# Controller.net
KiCad netlist of a schematic drawn in EAGLE
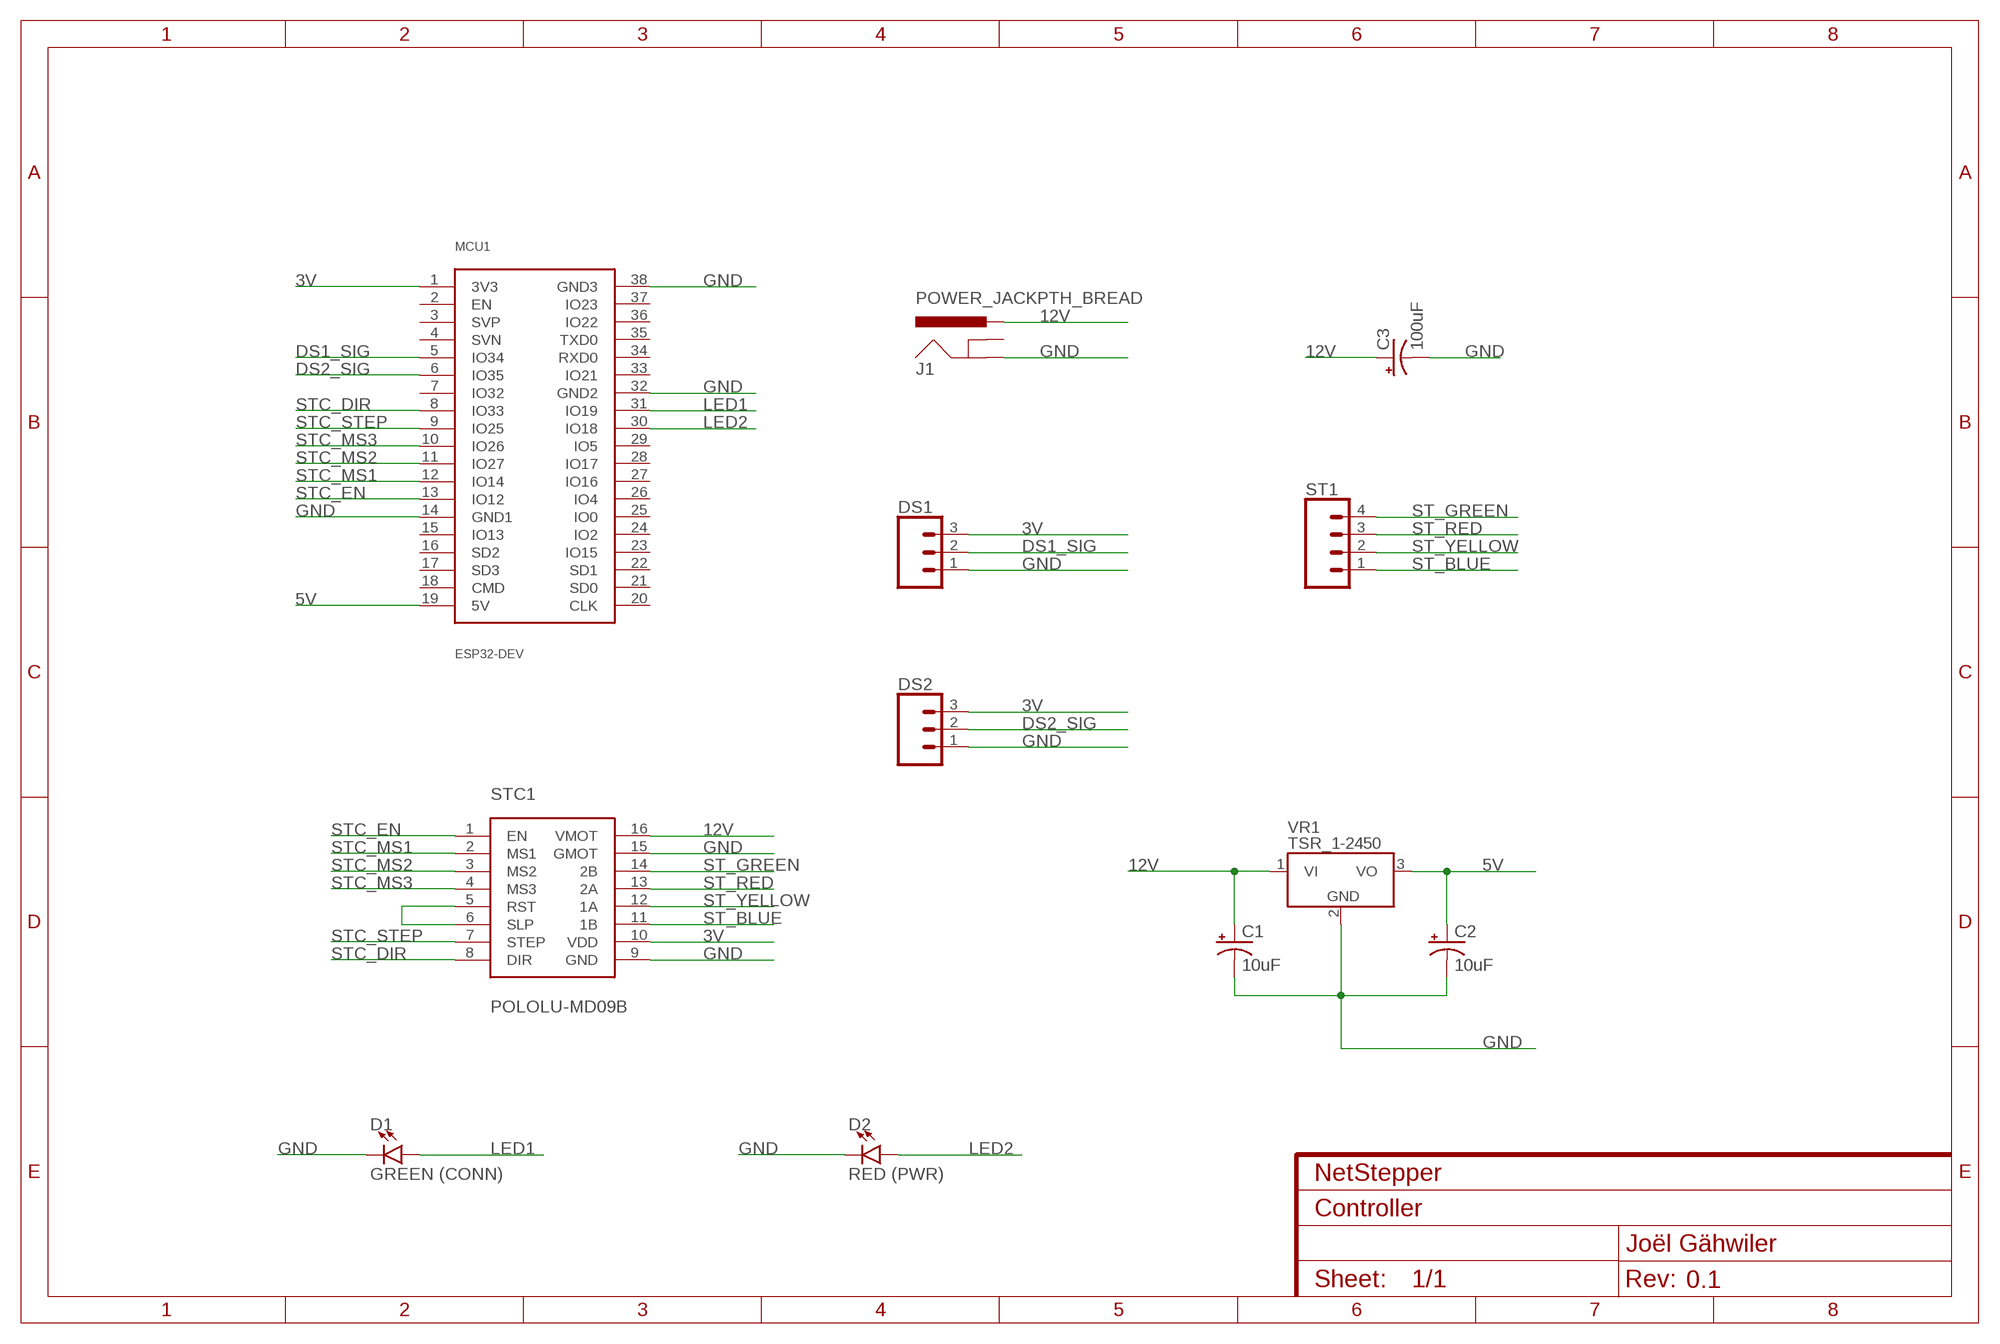
[diagram p0: schematic, sheet 1]

(export (version "E")
  (design (tool "Eeschema 10.0.6"))
  (components
    (comp (ref "C1")
      (value "10uF")
      (footprint "eagle-import:E2-5")
      (libsource (lib "eagle-import") (part "CPOL-USE2-5"))
    )
    (comp (ref "C2")
      (value "10uF")
      (footprint "eagle-import:E2-5")
      (libsource (lib "eagle-import") (part "CPOL-USE2-5"))
    )
    (comp (ref "C3")
      (value "100uF")
      (footprint "eagle-import:E2-5")
      (libsource (lib "eagle-import") (part "CPOL-USE2-5"))
    )
    (comp (ref "D1")
      (value "GREEN (CONN)")
      (footprint "eagle-import:LED_5MM")
      (libsource (lib "eagle-import") (part "LED5MM"))
    )
    (comp (ref "D2")
      (value "RED (PWR)")
      (footprint "eagle-import:LED_5MM")
      (libsource (lib "eagle-import") (part "LED5MM"))
    )
    (comp (ref "DS1")
      (value "CONN_03LONGPADS")
      (footprint "eagle-import:1X03_LONGPADS")
      (libsource (lib "eagle-import") (part "CONN_03LONGPADS"))
    )
    (comp (ref "DS2")
      (value "CONN_03LONGPADS")
      (footprint "eagle-import:1X03_LONGPADS")
      (libsource (lib "eagle-import") (part "CONN_03LONGPADS"))
    )
    (comp (ref "J1")
      (value "POWER_JACKPTH_BREAD")
      (footprint "eagle-import:POWER_JACK_PTH_BREAD")
      (libsource (lib "eagle-import") (part "POWER_JACKPTH_BREAD"))
    )
    (comp (ref "MCU1")
      (value "ESP32-DEV")
      (footprint "eagle-import:ESP32-DEV")
      (libsource (lib "eagle-import") (part "ESP32-DEV"))
    )
    (comp (ref "ST1")
      (value "CONN_04LONGPADS")
      (footprint "eagle-import:1X04_LONGPADS")
      (libsource (lib "eagle-import") (part "CONN_04LONGPADS"))
    )
    (comp (ref "STC1")
      (value "POLOLU-MD09B")
      (footprint "eagle-import:POLOLU-MD09B")
      (libsource (lib "eagle-import") (part "POLOLU-MD09B"))
    )
    (comp (ref "VR1")
      (value "TSR_1-2450")
      (footprint "eagle-import:TSR-1")
      (libsource (lib "eagle-import") (part "TSR_1-2450"))
    )
  )
  (nets
    (net (code "1") (name "/3V") (class "Default")
      (node (ref "DS1") (pin "3") (pinfunction "3_3") (pintype "passive"))
      (node (ref "DS2") (pin "3") (pinfunction "3_3") (pintype "passive"))
      (node (ref "MCU1") (pin "1") (pinfunction "3V3_1") (pintype "bidirectional"))
      (node (ref "STC1") (pin "10") (pinfunction "VDD_10") (pintype "bidirectional"))
    )
    (net (code "2") (name "/5V") (class "Default")
      (node (ref "C2") (pin "+") (pinfunction "+_+") (pintype "passive"))
      (node (ref "MCU1") (pin "19") (pinfunction "5V_19") (pintype "bidirectional"))
      (node (ref "VR1") (pin "3") (pinfunction "VO_3") (pintype "power_in"))
    )
    (net (code "3") (name "/12V") (class "Default")
      (node (ref "C1") (pin "+") (pinfunction "+_+") (pintype "passive"))
      (node (ref "C3") (pin "+") (pinfunction "+_+") (pintype "passive"))
      (node (ref "J1") (pin "PWR") (pinfunction "PWR_PWR") (pintype "bidirectional"))
      (node (ref "STC1") (pin "16") (pinfunction "VMOT_16") (pintype "bidirectional"))
      (node (ref "VR1") (pin "1") (pinfunction "VI_1") (pintype "power_in"))
    )
    (net (code "4") (name "/DS1_SIG") (class "Default")
      (node (ref "DS1") (pin "2") (pinfunction "2_2") (pintype "passive"))
      (node (ref "MCU1") (pin "5") (pinfunction "IO34_5") (pintype "bidirectional"))
    )
    (net (code "5") (name "/DS2_SIG") (class "Default")
      (node (ref "DS2") (pin "2") (pinfunction "2_2") (pintype "passive"))
      (node (ref "MCU1") (pin "6") (pinfunction "IO35_6") (pintype "bidirectional"))
    )
    (net (code "6") (name "/GND") (class "Default")
      (node (ref "C1") (pin "-") (pinfunction "-_-") (pintype "passive"))
      (node (ref "C2") (pin "-") (pinfunction "-_-") (pintype "passive"))
      (node (ref "C3") (pin "-") (pinfunction "-_-") (pintype "passive"))
      (node (ref "D1") (pin "K") (pinfunction "C_K") (pintype "passive"))
      (node (ref "D2") (pin "K") (pinfunction "C_K") (pintype "passive"))
      (node (ref "DS1") (pin "1") (pinfunction "1_1") (pintype "passive"))
      (node (ref "DS2") (pin "1") (pinfunction "1_1") (pintype "passive"))
      (node (ref "J1") (pin "GND") (pinfunction "GND_GND") (pintype "bidirectional"))
      (node (ref "MCU1") (pin "14") (pinfunction "GND1_14") (pintype "bidirectional"))
      (node (ref "MCU1") (pin "32") (pinfunction "GND2_32") (pintype "bidirectional"))
      (node (ref "MCU1") (pin "38") (pinfunction "GND3_38") (pintype "bidirectional"))
      (node (ref "STC1") (pin "15") (pinfunction "GMOT_15") (pintype "bidirectional"))
      (node (ref "STC1") (pin "9") (pinfunction "GND_9") (pintype "bidirectional"))
      (node (ref "VR1") (pin "2") (pinfunction "GND_2") (pintype "power_in"))
    )
    (net (code "7") (name "/LED1") (class "Default")
      (node (ref "D1") (pin "A") (pinfunction "A_A") (pintype "passive"))
      (node (ref "MCU1") (pin "31") (pinfunction "IO19_31") (pintype "bidirectional"))
    )
    (net (code "8") (name "/LED2") (class "Default")
      (node (ref "D2") (pin "A") (pinfunction "A_A") (pintype "passive"))
      (node (ref "MCU1") (pin "30") (pinfunction "IO18_30") (pintype "bidirectional"))
    )
    (net (code "9") (name "/STC_DIR") (class "Default")
      (node (ref "MCU1") (pin "8") (pinfunction "IO33_8") (pintype "bidirectional"))
      (node (ref "STC1") (pin "8") (pinfunction "DIR_8") (pintype "bidirectional"))
    )
    (net (code "10") (name "/STC_EN") (class "Default")
      (node (ref "MCU1") (pin "13") (pinfunction "IO12_13") (pintype "bidirectional"))
      (node (ref "STC1") (pin "1") (pinfunction "EN_1") (pintype "bidirectional"))
    )
    (net (code "11") (name "/STC_MS1") (class "Default")
      (node (ref "MCU1") (pin "12") (pinfunction "IO14_12") (pintype "bidirectional"))
      (node (ref "STC1") (pin "2") (pinfunction "MS1_2") (pintype "bidirectional"))
    )
    (net (code "12") (name "/STC_MS2") (class "Default")
      (node (ref "MCU1") (pin "11") (pinfunction "IO27_11") (pintype "bidirectional"))
      (node (ref "STC1") (pin "3") (pinfunction "MS2_3") (pintype "bidirectional"))
    )
    (net (code "13") (name "/STC_MS3") (class "Default")
      (node (ref "MCU1") (pin "10") (pinfunction "IO26_10") (pintype "bidirectional"))
      (node (ref "STC1") (pin "4") (pinfunction "MS3_4") (pintype "bidirectional"))
    )
    (net (code "14") (name "/STC_STEP") (class "Default")
      (node (ref "MCU1") (pin "9") (pinfunction "IO25_9") (pintype "bidirectional"))
      (node (ref "STC1") (pin "7") (pinfunction "STEP_7") (pintype "bidirectional"))
    )
    (net (code "15") (name "/ST_BLUE") (class "Default")
      (node (ref "ST1") (pin "1") (pinfunction "1_1") (pintype "passive"))
      (node (ref "STC1") (pin "11") (pinfunction "1B_11") (pintype "bidirectional"))
    )
    (net (code "16") (name "/ST_GREEN") (class "Default")
      (node (ref "ST1") (pin "4") (pinfunction "4_4") (pintype "passive"))
      (node (ref "STC1") (pin "14") (pinfunction "2B_14") (pintype "bidirectional"))
    )
    (net (code "17") (name "/ST_RED") (class "Default")
      (node (ref "ST1") (pin "3") (pinfunction "3_3") (pintype "passive"))
      (node (ref "STC1") (pin "13") (pinfunction "2A_13") (pintype "bidirectional"))
    )
    (net (code "18") (name "/ST_YELLOW") (class "Default")
      (node (ref "ST1") (pin "2") (pinfunction "2_2") (pintype "passive"))
      (node (ref "STC1") (pin "12") (pinfunction "1A_12") (pintype "bidirectional"))
    )
    (net (code "19") (name "Net-(STC1-RST)") (class "Default")
      (node (ref "STC1") (pin "5") (pinfunction "RST_5") (pintype "bidirectional"))
      (node (ref "STC1") (pin "6") (pinfunction "SLP_6") (pintype "bidirectional"))
    )
    (net (code "20") (name "unconnected-(J1-PadGNDBREAK)") (class "Default")
      (node (ref "J1") (pin "GNDBREAK") (pinfunction "GNDBREAK_GNDBREAK") (pintype "bidirectional"))
    )
    (net (code "21") (name "unconnected-(MCU1-CLK-Pad20)") (class "Default")
      (node (ref "MCU1") (pin "20") (pinfunction "CLK_20") (pintype "bidirectional"))
    )
    (net (code "22") (name "unconnected-(MCU1-CMD-Pad18)") (class "Default")
      (node (ref "MCU1") (pin "18") (pinfunction "CMD_18") (pintype "bidirectional"))
    )
    (net (code "23") (name "unconnected-(MCU1-EN-Pad2)") (class "Default")
      (node (ref "MCU1") (pin "2") (pinfunction "EN_2") (pintype "bidirectional"))
    )
    (net (code "24") (name "unconnected-(MCU1-IO0-Pad25)") (class "Default")
      (node (ref "MCU1") (pin "25") (pinfunction "IO0_25") (pintype "bidirectional"))
    )
    (net (code "25") (name "unconnected-(MCU1-IO2-Pad24)") (class "Default")
      (node (ref "MCU1") (pin "24") (pinfunction "IO2_24") (pintype "bidirectional"))
    )
    (net (code "26") (name "unconnected-(MCU1-IO4-Pad26)") (class "Default")
      (node (ref "MCU1") (pin "26") (pinfunction "IO4_26") (pintype "bidirectional"))
    )
    (net (code "27") (name "unconnected-(MCU1-IO5-Pad29)") (class "Default")
      (node (ref "MCU1") (pin "29") (pinfunction "IO5_29") (pintype "bidirectional"))
    )
    (net (code "28") (name "unconnected-(MCU1-IO13-Pad15)") (class "Default")
      (node (ref "MCU1") (pin "15") (pinfunction "IO13_15") (pintype "bidirectional"))
    )
    (net (code "29") (name "unconnected-(MCU1-IO15-Pad23)") (class "Default")
      (node (ref "MCU1") (pin "23") (pinfunction "IO15_23") (pintype "bidirectional"))
    )
    (net (code "30") (name "unconnected-(MCU1-IO16-Pad27)") (class "Default")
      (node (ref "MCU1") (pin "27") (pinfunction "IO16_27") (pintype "bidirectional"))
    )
    (net (code "31") (name "unconnected-(MCU1-IO17-Pad28)") (class "Default")
      (node (ref "MCU1") (pin "28") (pinfunction "IO17_28") (pintype "bidirectional"))
    )
    (net (code "32") (name "unconnected-(MCU1-IO21-Pad33)") (class "Default")
      (node (ref "MCU1") (pin "33") (pinfunction "IO21_33") (pintype "bidirectional"))
    )
    (net (code "33") (name "unconnected-(MCU1-IO22-Pad36)") (class "Default")
      (node (ref "MCU1") (pin "36") (pinfunction "IO22_36") (pintype "bidirectional"))
    )
    (net (code "34") (name "unconnected-(MCU1-IO23-Pad37)") (class "Default")
      (node (ref "MCU1") (pin "37") (pinfunction "IO23_37") (pintype "bidirectional"))
    )
    (net (code "35") (name "unconnected-(MCU1-IO32-Pad7)") (class "Default")
      (node (ref "MCU1") (pin "7") (pinfunction "IO32_7") (pintype "bidirectional"))
    )
    (net (code "36") (name "unconnected-(MCU1-RXD0-Pad34)") (class "Default")
      (node (ref "MCU1") (pin "34") (pinfunction "RXD0_34") (pintype "bidirectional"))
    )
    (net (code "37") (name "unconnected-(MCU1-SD0-Pad21)") (class "Default")
      (node (ref "MCU1") (pin "21") (pinfunction "SD0_21") (pintype "bidirectional"))
    )
    (net (code "38") (name "unconnected-(MCU1-SD1-Pad22)") (class "Default")
      (node (ref "MCU1") (pin "22") (pinfunction "SD1_22") (pintype "bidirectional"))
    )
    (net (code "39") (name "unconnected-(MCU1-SD2-Pad16)") (class "Default")
      (node (ref "MCU1") (pin "16") (pinfunction "SD2_16") (pintype "bidirectional"))
    )
    (net (code "40") (name "unconnected-(MCU1-SD3-Pad17)") (class "Default")
      (node (ref "MCU1") (pin "17") (pinfunction "SD3_17") (pintype "bidirectional"))
    )
    (net (code "41") (name "unconnected-(MCU1-SVN-Pad4)") (class "Default")
      (node (ref "MCU1") (pin "4") (pinfunction "SVN_4") (pintype "bidirectional"))
    )
    (net (code "42") (name "unconnected-(MCU1-SVP-Pad3)") (class "Default")
      (node (ref "MCU1") (pin "3") (pinfunction "SVP_3") (pintype "bidirectional"))
    )
    (net (code "43") (name "unconnected-(MCU1-TXD0-Pad35)") (class "Default")
      (node (ref "MCU1") (pin "35") (pinfunction "TXD0_35") (pintype "bidirectional"))
    )
  )
)
